# SCH-esp32.net
KiCad netlist of a schematic drawn in Altium Designer
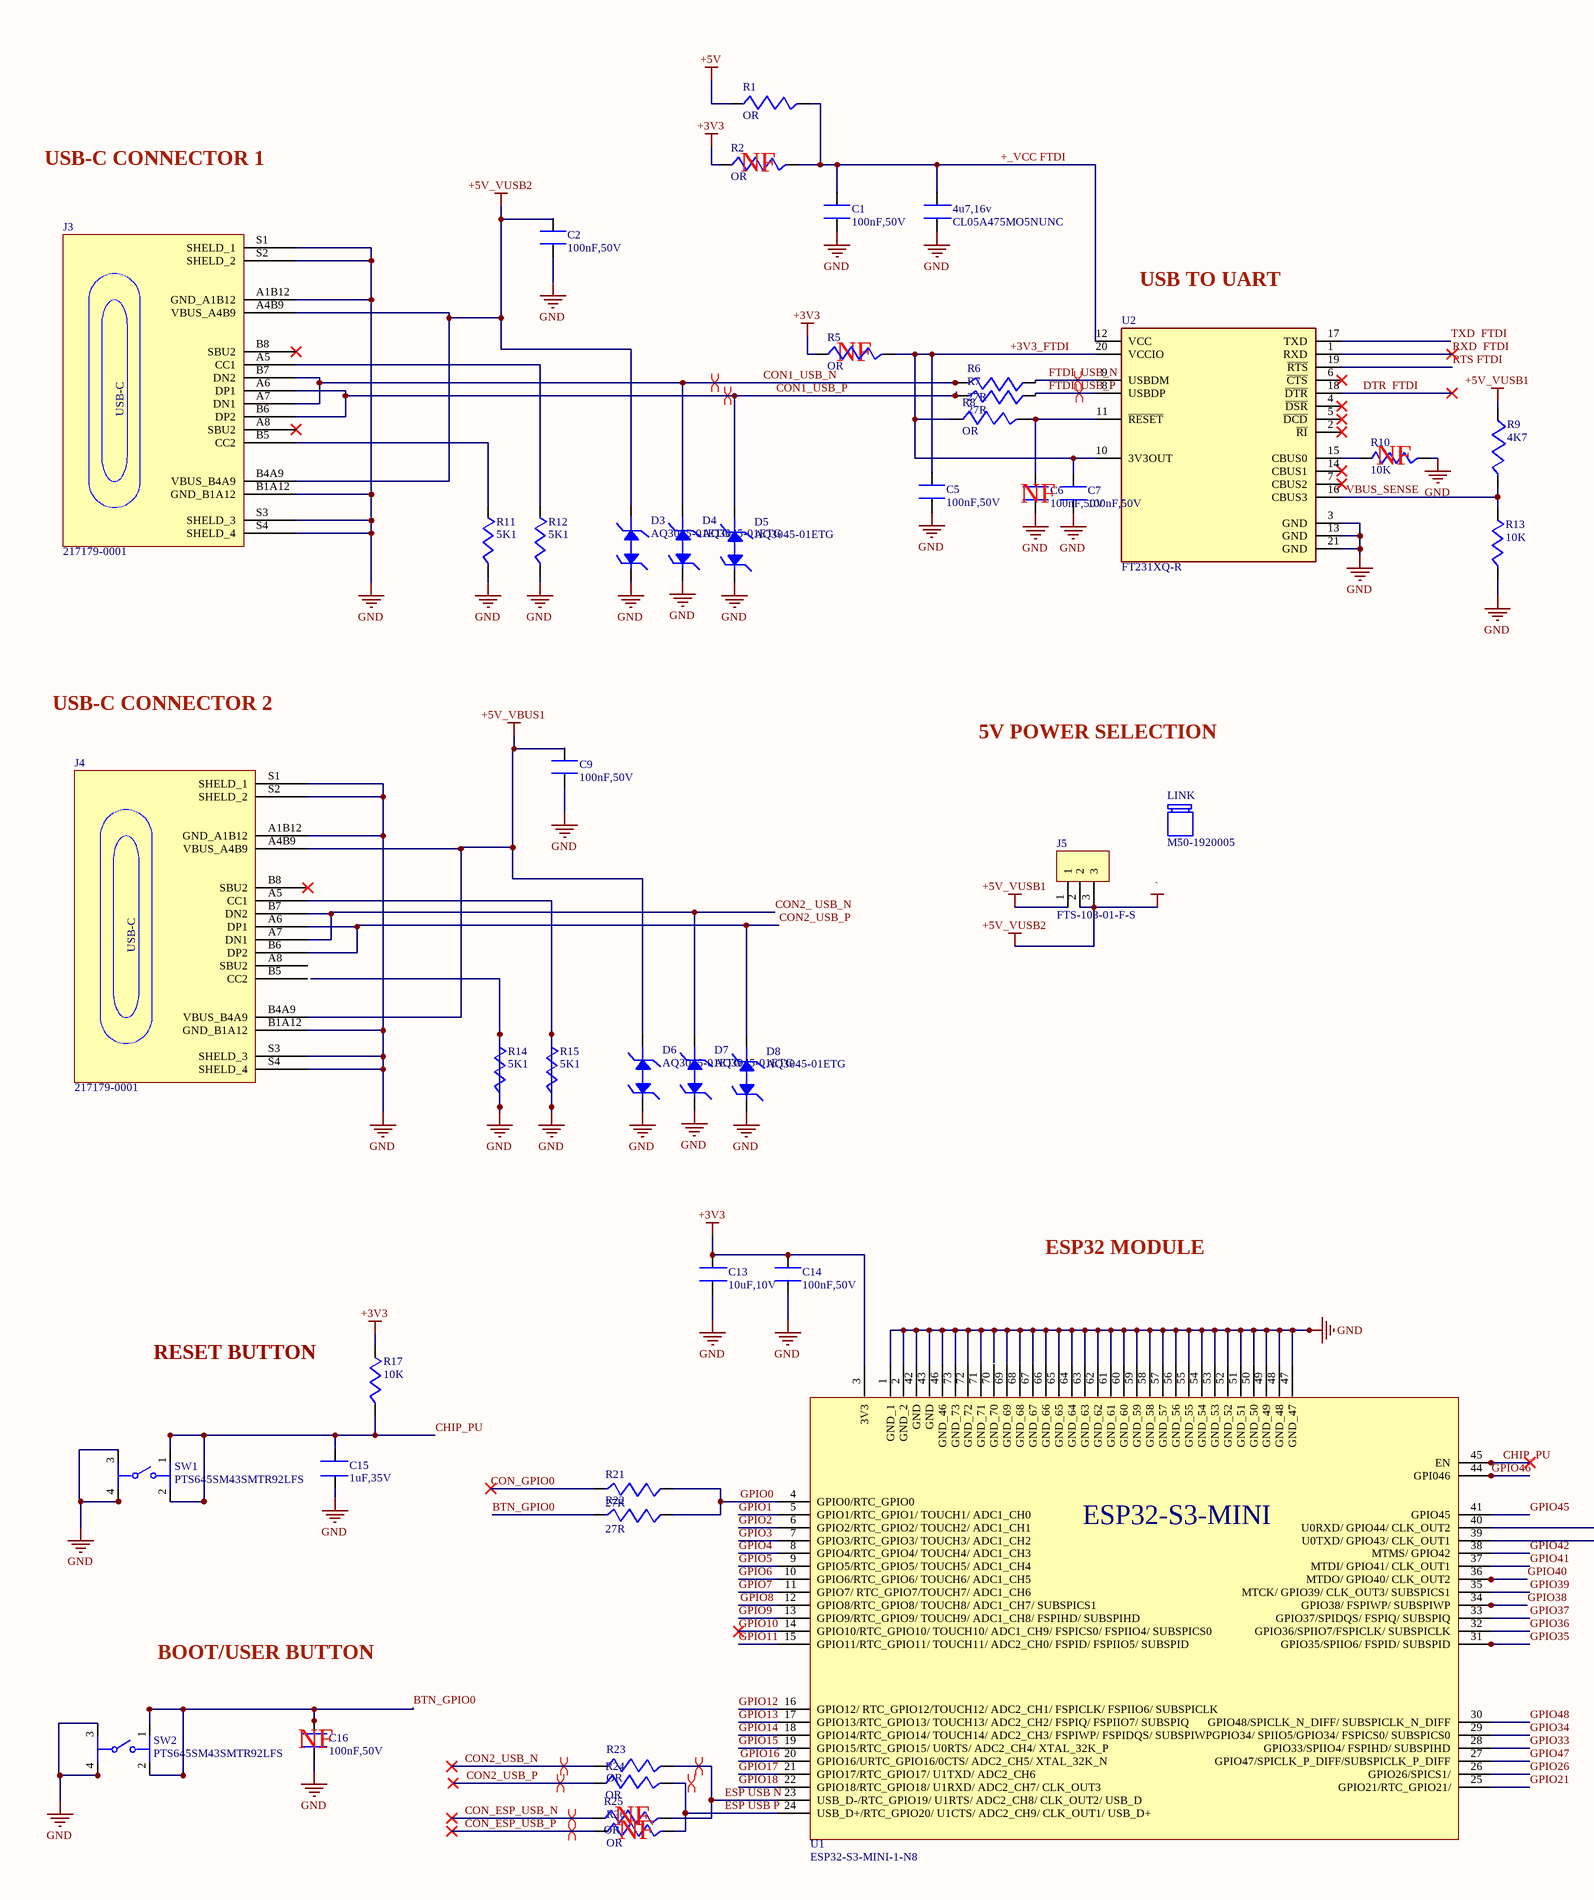
[diagram p0: SCH-esp32.SchDoc, left]
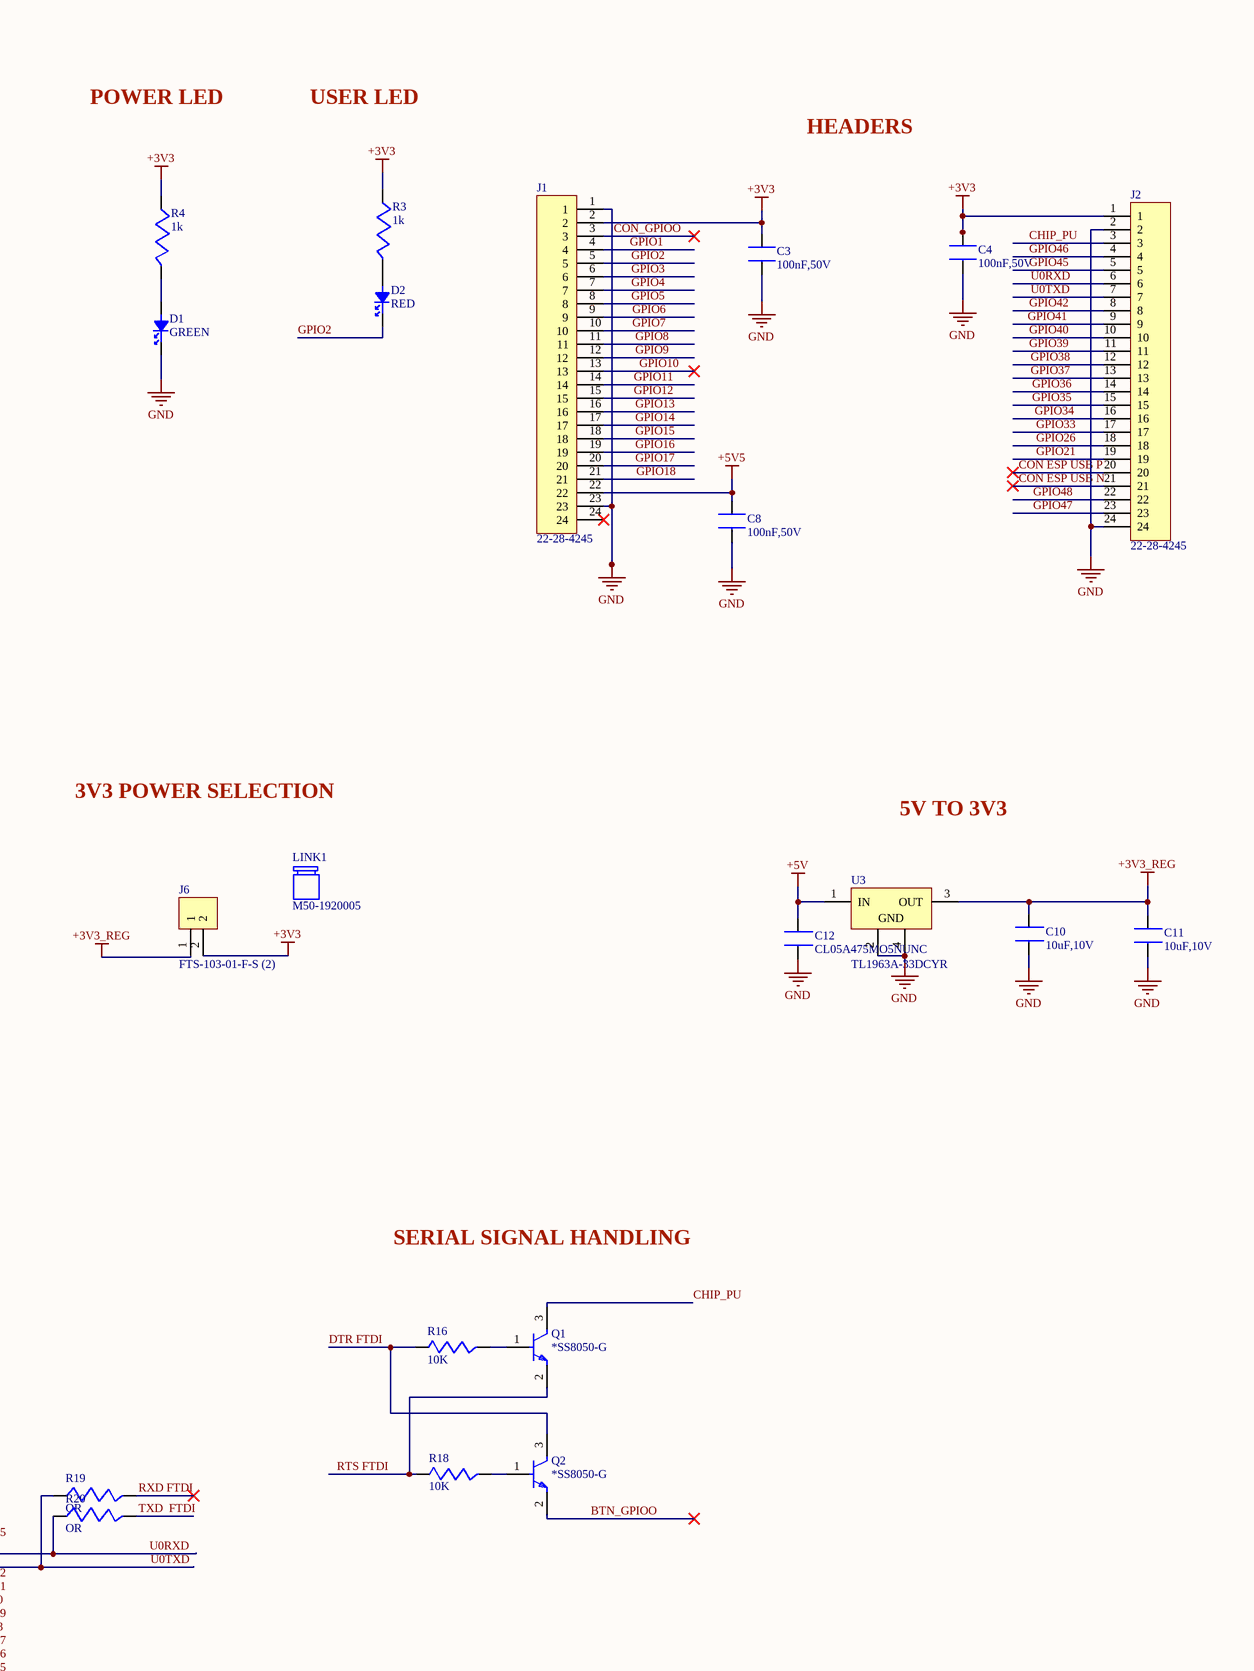
[diagram p1: SCH-esp32.SchDoc, right]

(export (version "E")
  (design (tool "Eeschema 10.0.6"))
  (components
    (comp (ref "4u7,16v")
      (value "CL05A475MO5NUNC")
      (footprint "CAPC1005X55N")
      (description "1276-6836-6-ND")
      (fields (field (name "MANUFACTURER") "Samsung Electro-Mechanics") (field (name "TOLERANCE") "20%"))
      (libsource (lib "Schlib-esp32") (part "CL05A475MO5NUNC"))
    )
    (comp (ref "C1")
      (value "100nF,50V")
      (footprint "CAPC1005X55N")
      (description "CAP CER 0.1UF 50V X7R 0402")
      (fields
        (field (name "MANUFACTURER") "Samsung Electro-Mechanics")
        (field (name "MANUFACTURER PART NUMBER") "CL05B104KB5NNNC")
      )
      (libsource (lib "Schlib-esp32") (part "CL05B104KB5NNNC"))
    )
    (comp (ref "C2")
      (value "100nF,50V")
      (footprint "CAPC1005X55N")
      (description "CAP CER 0.1UF 50V X7R 0402")
      (fields
        (field (name "MANUFACTURER") "Samsung Electro-Mechanics")
        (field (name "MANUFACTURER PART NUMBER") "CL05B104KB5NNNC")
      )
      (libsource (lib "Schlib-esp32") (part "CL05B104KB5NNNC"))
    )
    (comp (ref "C3")
      (value "100nF,50V")
      (footprint "CAPC1005X55N")
      (description "CAP CER 0.1UF 50V X7R 0402")
      (fields
        (field (name "MANUFACTURER") "Samsung Electro-Mechanics")
        (field (name "MANUFACTURER PART NUMBER") "CL05B104KB5NNNC")
      )
      (libsource (lib "Schlib-esp32") (part "CL05B104KB5NNNC"))
    )
    (comp (ref "C4")
      (value "100nF,50V")
      (footprint "CAPC1005X55N")
      (description "CAP CER 0.1UF 50V X7R 0402")
      (fields
        (field (name "MANUFACTURER") "Samsung Electro-Mechanics")
        (field (name "MANUFACTURER PART NUMBER") "CL05B104KB5NNNC")
      )
      (libsource (lib "Schlib-esp32") (part "CL05B104KB5NNNC"))
    )
    (comp (ref "C5")
      (value "100nF,50V")
      (footprint "CAPC1005X55N")
      (description "CAP CER 0.1UF 50V X7R 0402")
      (fields
        (field (name "MANUFACTURER") "Samsung Electro-Mechanics")
        (field (name "MANUFACTURER PART NUMBER") "CL05B104KB5NNNC")
      )
      (libsource (lib "Schlib-esp32") (part "CL05B104KB5NNNC"))
    )
    (comp (ref "C6")
      (value "100nF,50V")
      (footprint "CAPC1005X55N")
      (description "CAP CER 0.1UF 50V X7R 0402")
      (fields
        (field (name "MANUFACTURER") "Samsung Electro-Mechanics")
        (field (name "MANUFACTURER PART NUMBER") "CL05B104KB5NNNC")
      )
      (libsource (lib "Schlib-esp32") (part "CL05B104KB5NNNC"))
    )
    (comp (ref "C7")
      (value "100nF,50V")
      (footprint "CAPC1005X55N")
      (description "CAP CER 0.1UF 50V X7R 0402")
      (fields
        (field (name "MANUFACTURER") "Samsung Electro-Mechanics")
        (field (name "MANUFACTURER PART NUMBER") "CL05B104KB5NNNC")
      )
      (libsource (lib "Schlib-esp32") (part "CL05B104KB5NNNC"))
    )
    (comp (ref "C8")
      (value "100nF,50V")
      (footprint "CAPC1005X55N")
      (description "CAP CER 0.1UF 50V X7R 0402")
      (fields
        (field (name "MANUFACTURER") "Samsung Electro-Mechanics")
        (field (name "MANUFACTURER PART NUMBER") "CL05B104KB5NNNC")
      )
      (libsource (lib "Schlib-esp32") (part "CL05B104KB5NNNC"))
    )
    (comp (ref "C9")
      (value "100nF,50V")
      (footprint "CAPC1005X55N")
      (description "CAP CER 0.1UF 50V X7R 0402")
      (fields
        (field (name "MANUFACTURER") "Samsung Electro-Mechanics")
        (field (name "MANUFACTURER PART NUMBER") "CL05B104KB5NNNC")
      )
      (libsource (lib "Schlib-esp32") (part "CL05B104KB5NNNC"))
    )
    (comp (ref "C10")
      (value "10uF,10V")
      (footprint "CAPC1005X55N")
      (description "10V 10uF X5R ±20% 0402 Multilayer Ceramic Capacitors MLCC - SMD/SMT ROHS")
      (fields
        (field (name "MANUFACTURER") "Samsung Electro-Mechanics")
        (field (name "MANUFACTURER PART NUMBER") "CL05A106MP8NUB8")
      )
      (libsource (lib "Schlib-esp32") (part "CL05A106MP8NUB8"))
    )
    (comp (ref "C11")
      (value "10uF,10V")
      (footprint "CAPC1005X55N")
      (description "10V 10uF X5R ±20% 0402 Multilayer Ceramic Capacitors MLCC - SMD/SMT ROHS")
      (fields
        (field (name "MANUFACTURER") "Samsung Electro-Mechanics")
        (field (name "MANUFACTURER PART NUMBER") "CL05A106MP8NUB8")
      )
      (libsource (lib "Schlib-esp32") (part "CL05A106MP8NUB8"))
    )
    (comp (ref "C12")
      (value "CL05A475MO5NUNC")
      (footprint "CAPC1005X55N")
      (description "1276-6836-6-ND")
      (fields (field (name "MANUFACTURER") "Samsung Electro-Mechanics") (field (name "TOLERANCE") "20%"))
      (libsource (lib "Schlib-esp32") (part "CL05A475MO5NUNC"))
    )
    (comp (ref "C13")
      (value "10uF,10V")
      (footprint "CAPC1005X55N")
      (description "10V 10uF X5R ±20% 0402 Multilayer Ceramic Capacitors MLCC - SMD/SMT ROHS")
      (fields
        (field (name "MANUFACTURER") "Samsung Electro-Mechanics")
        (field (name "MANUFACTURER PART NUMBER") "CL05A106MP8NUB8")
      )
      (libsource (lib "Schlib-esp32") (part "CL05A106MP8NUB8"))
    )
    (comp (ref "C14")
      (value "100nF,50V")
      (footprint "CAPC1005X55N")
      (description "CAP CER 0.1UF 50V X7R 0402")
      (fields
        (field (name "MANUFACTURER") "Samsung Electro-Mechanics")
        (field (name "MANUFACTURER PART NUMBER") "CL05B104KB5NNNC")
      )
      (libsource (lib "Schlib-esp32") (part "CL05B104KB5NNNC"))
    )
    (comp (ref "C15")
      (value "1uF,35V")
      (footprint "CAPC1005X55N")
      (description "CAP CER 1UF 35V X5R 0402")
      (fields
        (field (name "MANUFACTURER") "Samsung Electro-Mechanics")
        (field (name "MANUFACTURER PART NUMBER") "CL05A105KL5NRNC")
      )
      (libsource (lib "Schlib-esp32") (part "CL05A105KL5NRNC"))
    )
    (comp (ref "C16")
      (value "100nF,50V")
      (footprint "CAPC1005X55N")
      (description "CAP CER 0.1UF 50V X7R 0402")
      (fields
        (field (name "MANUFACTURER") "Samsung Electro-Mechanics")
        (field (name "MANUFACTURER PART NUMBER") "CL05B104KB5NNNC")
      )
      (libsource (lib "Schlib-esp32") (part "CL05B104KB5NNNC"))
    )
    (comp (ref "D1")
      (value "GREEN")
      (footprint "LED0402G")
      (description "LED GREEN 0402 SMD")
      (fields
        (field (name "MANUFACTURER") "Vishay")
        (field (name "MANUFACTURER PART NUMBER") "VLMTG1500-GS08")
      )
      (libsource (lib "Schlib-esp32") (part "VLMTG1500-GS08"))
    )
    (comp (ref "D2")
      (value "RED")
      (footprint "LED0402R")
      (description "LED RED 0402 SMD")
      (fields
        (field (name "MANUFACTURER") "Vishay")
        (field (name "MANUFACTURER PART NUMBER") "VLMS1500-GS08")
      )
      (libsource (lib "Schlib-esp32") (part "VLMS1500-GS08"))
    )
    (comp (ref "D3")
      (value "AQ3045-01ETG")
      (footprint "SOD882")
      (description "TVS DIODE 5.3VWM 12VC SOD882")
      (fields (field (name "MANUFACTURER") "Littelfuse"))
      (libsource (lib "Schlib-esp32") (part "AQ3045-01ETG"))
    )
    (comp (ref "D4")
      (value "AQ3045-01ETG")
      (footprint "SOD882")
      (description "TVS DIODE 5.3VWM 12VC SOD882")
      (fields (field (name "MANUFACTURER") "Littelfuse"))
      (libsource (lib "Schlib-esp32") (part "AQ3045-01ETG"))
    )
    (comp (ref "D5")
      (value "AQ3045-01ETG")
      (footprint "SOD882")
      (description "TVS DIODE 5.3VWM 12VC SOD882")
      (fields (field (name "MANUFACTURER") "Littelfuse"))
      (libsource (lib "Schlib-esp32") (part "AQ3045-01ETG"))
    )
    (comp (ref "D6")
      (value "AQ3045-01ETG")
      (footprint "SOD882")
      (description "TVS DIODE 5.3VWM 12VC SOD882")
      (fields (field (name "MANUFACTURER") "Littelfuse"))
      (libsource (lib "Schlib-esp32") (part "AQ3045-01ETG"))
    )
    (comp (ref "D7")
      (value "AQ3045-01ETG")
      (footprint "SOD882")
      (description "TVS DIODE 5.3VWM 12VC SOD882")
      (fields (field (name "MANUFACTURER") "Littelfuse"))
      (libsource (lib "Schlib-esp32") (part "AQ3045-01ETG"))
    )
    (comp (ref "D8")
      (value "AQ3045-01ETG")
      (footprint "SOD882")
      (description "TVS DIODE 5.3VWM 12VC SOD882")
      (fields (field (name "MANUFACTURER") "Littelfuse"))
      (libsource (lib "Schlib-esp32") (part "AQ3045-01ETG"))
    )
    (comp (ref "J1")
      (value "22-28-4245")
      (footprint "HDR_1X24_2.54MM")
      (description "CONN HEADER VERT 24POS 2.54MM")
      (fields (field (name "MANUFACTURER") "Molex"))
      (libsource (lib "") (part "22-28-4245_1"))
    )
    (comp (ref "J2")
      (value "22-28-4245")
      (footprint "HDR_1X24_2.54MM")
      (description "CONN HEADER VERT 24POS 2.54MM")
      (fields (field (name "MANUFACTURER") "Molex"))
      (libsource (lib "Schlib-esp32") (part "22-28-4245"))
    )
    (comp (ref "J3")
      (value "217179-0001")
      (footprint "FP-2171790001-MFG")
      (description "USB Connector, USB Type C, USB 2.0, Receptacle, 16 Ways, Surface Mount, Through Hole Mount")
      (fields (field (name "MANUFACTURER") "Molex"))
      (libsource (lib "Schlib-esp32") (part "217179-0001"))
    )
    (comp (ref "J4")
      (value "217179-0001")
      (footprint "FP-2171790001-MFG")
      (description "USB Connector, USB Type C, USB 2.0, Receptacle, 16 Ways, Surface Mount, Through Hole Mount")
      (fields (field (name "MANUFACTURER") "Molex"))
      (libsource (lib "Schlib-esp32") (part "217179-0001"))
    )
    (comp (ref "J5")
      (value "FTS-103-01-F-S")
      (footprint "HDR_1X3_1.27MM")
      (description "CONN HEADER VERT 3POS 1.27MM")
      (fields (field (name "MANUFACTURER") "Samtec"))
      (libsource (lib "Schlib-esp32") (part "FTS-103-01-F-S"))
    )
    (comp (ref "J6")
      (value "FTS-103-01-F-S (2)")
      (footprint "HDR_1X2_1.27MM")
      (description "CONN HEADER VERT 3POS 1.27MM")
      (fields
        (field (name "MANUFACTURER") "Samtec")
        (field (name "MANUFACTURER PART NUMBER") "FTS-103-01-F-S")
      )
      (libsource (lib "Schlib-esp32") (part "FTS-103-01-F-S (2)"))
    )
    (comp (ref "LINK")
      (value "M50-1920005")
      (description "2 (1 x 2) Position Shunt Connector Red Closed Top 0.050\" (1.27mm) Gold")
      (fields (field (name "MANUFACTURER") "Harwin"))
      (libsource (lib "Schlib-esp32") (part "M50-1920005"))
    )
    (comp (ref "LINK1")
      (value "M50-1920005")
      (description "2 (1 x 2) Position Shunt Connector Red Closed Top 0.050\" (1.27mm) Gold")
      (fields (field (name "MANUFACTURER") "Harwin"))
      (libsource (lib "Schlib-esp32") (part "M50-1920005"))
    )
    (comp (ref "Q1")
      (value "*SS8050-G")
      (footprint "FP-SS8050-G-IPC_B")
      (description "TRANS NPN 25V 1.5A SOT-23-3")
      (fields (field (name "MANUFACTURER") "Comchip") (field (name "MANUFACTURER PART NUMBER") "SS8050-G"))
      (libsource (lib "Schlib-esp32") (part "SS8050-G"))
    )
    (comp (ref "Q2")
      (value "*SS8050-G")
      (footprint "FP-SS8050-G-IPC_B")
      (description "TRANS NPN 25V 1.5A SOT-23-3")
      (fields (field (name "MANUFACTURER") "Comchip") (field (name "MANUFACTURER PART NUMBER") "SS8050-G"))
      (libsource (lib "Schlib-esp32") (part "SS8050-G"))
    )
    (comp (ref "R1")
      (value "OR")
      (footprint "RESC1005X37N")
      (description "RES 0 OHM JUMPER 1/16W 0402")
      (fields
        (field (name "MANUFACTURER") "Yageo Group")
        (field (name "MANUFACTURER PART NUMBER") "RC0402JR-070RL")
      )
      (libsource (lib "Schlib-esp32") (part "RC0402JR-070RL"))
    )
    (comp (ref "R2")
      (value "OR")
      (footprint "RESC1005X37N")
      (description "RES 0 OHM JUMPER 1/16W 0402")
      (fields
        (field (name "MANUFACTURER") "Yageo Group")
        (field (name "MANUFACTURER PART NUMBER") "RC0402JR-070RL")
      )
      (libsource (lib "Schlib-esp32") (part "RC0402JR-070RL"))
    )
    (comp (ref "R3")
      (value "1k")
      (footprint "RESC1005X37N")
      (description "RES 1K OHM 1% 1/16W 0402")
      (fields
        (field (name "MANUFACTURER") "Vishay")
        (field (name "MANUFACTURER PART NUMBER") "MCS0402PD1001DE500")
      )
      (libsource (lib "Schlib-esp32") (part "MCS0402PD1001DE500"))
    )
    (comp (ref "R4")
      (value "1k")
      (footprint "RESC1005X37N")
      (description "RES 1K OHM 1% 1/16W 0402")
      (fields
        (field (name "MANUFACTURER") "Vishay")
        (field (name "MANUFACTURER PART NUMBER") "MCS0402PD1001DE500")
      )
      (libsource (lib "Schlib-esp32") (part "MCS0402PD1001DE500"))
    )
    (comp (ref "R5")
      (value "OR")
      (footprint "RESC1005X37N")
      (description "RES 0 OHM JUMPER 1/16W 0402")
      (fields
        (field (name "MANUFACTURER") "Yageo Group")
        (field (name "MANUFACTURER PART NUMBER") "RC0402JR-070RL")
      )
      (libsource (lib "Schlib-esp32") (part "RC0402JR-070RL"))
    )
    (comp (ref "R6")
      (value "27R")
      (footprint "RESC1005X37N")
      (description "RES 27 OHM 1% 1/16W 0402")
      (fields
        (field (name "MANUFACTURER") "Yageo Group")
        (field (name "MANUFACTURER PART NUMBER") "RC0402FR-0727RL")
      )
      (libsource (lib "Schlib-esp32") (part "RC0402FR-0727RL"))
    )
    (comp (ref "R7")
      (value "27R")
      (footprint "RESC1005X37N")
      (description "RES 27 OHM 1% 1/16W 0402")
      (fields
        (field (name "MANUFACTURER") "Yageo Group")
        (field (name "MANUFACTURER PART NUMBER") "RC0402FR-0727RL")
      )
      (libsource (lib "Schlib-esp32") (part "RC0402FR-0727RL"))
    )
    (comp (ref "R8")
      (value "OR")
      (footprint "RESC1005X37N")
      (description "RES 0 OHM JUMPER 1/16W 0402")
      (fields
        (field (name "MANUFACTURER") "Yageo Group")
        (field (name "MANUFACTURER PART NUMBER") "RC0402JR-070RL")
      )
      (libsource (lib "Schlib-esp32") (part "RC0402JR-070RL"))
    )
    (comp (ref "R9")
      (value "4K7")
      (footprint "RESC1005X37N")
      (description "RES 4.7K OHM 1% 1/16W 0402")
      (fields
        (field (name "MANUFACTURER") "Yageo Group")
        (field (name "MANUFACTURER PART NUMBER") "AC0603JR-134K7L")
      )
      (libsource (lib "Schlib-esp32") (part "AC0603JR-134K7L"))
    )
    (comp (ref "R10")
      (value "10K")
      (footprint "RESC1005X37N")
      (description "RES SMD 10K OHM 1% 1/16W 0402")
      (fields
        (field (name "MANUFACTURER") "Yageo Group")
        (field (name "MANUFACTURER PART NUMBER") "AC0402FR-0710KL")
      )
      (libsource (lib "Schlib-esp32") (part "AC0402FR-0710KL"))
    )
    (comp (ref "R11")
      (value "5K1")
      (footprint "RESC1005X37N")
      (description "RES SMD 5.1K OHM 1% 1/16W 0402")
      (fields
        (field (name "MANUFACTURER") "Yageo Group")
        (field (name "MANUFACTURER PART NUMBER") "AC0402FR-075K1L")
      )
      (libsource (lib "Schlib-esp32") (part "AC0402FR-075K1L"))
    )
    (comp (ref "R12")
      (value "5K1")
      (footprint "RESC1005X37N")
      (description "RES SMD 5.1K OHM 1% 1/16W 0402")
      (fields
        (field (name "MANUFACTURER") "Yageo Group")
        (field (name "MANUFACTURER PART NUMBER") "AC0402FR-075K1L")
      )
      (libsource (lib "Schlib-esp32") (part "AC0402FR-075K1L"))
    )
    (comp (ref "R13")
      (value "10K")
      (footprint "RESC1005X37N")
      (description "RES SMD 10K OHM 1% 1/16W 0402")
      (fields
        (field (name "MANUFACTURER") "Yageo Group")
        (field (name "MANUFACTURER PART NUMBER") "AC0402FR-0710KL")
      )
      (libsource (lib "Schlib-esp32") (part "AC0402FR-0710KL"))
    )
    (comp (ref "R14")
      (value "5K1")
      (footprint "RESC1005X37N")
      (description "RES SMD 5.1K OHM 1% 1/16W 0402")
      (fields
        (field (name "MANUFACTURER") "Yageo Group")
        (field (name "MANUFACTURER PART NUMBER") "AC0402FR-075K1L")
      )
      (libsource (lib "Schlib-esp32") (part "AC0402FR-075K1L"))
    )
    (comp (ref "R15")
      (value "5K1")
      (footprint "RESC1005X37N")
      (description "RES SMD 5.1K OHM 1% 1/16W 0402")
      (fields
        (field (name "MANUFACTURER") "Yageo Group")
        (field (name "MANUFACTURER PART NUMBER") "AC0402FR-075K1L")
      )
      (libsource (lib "Schlib-esp32") (part "AC0402FR-075K1L"))
    )
    (comp (ref "R16")
      (value "10K")
      (footprint "RESC1005X37N")
      (description "RES SMD 10K OHM 1% 1/16W 0402")
      (fields
        (field (name "MANUFACTURER") "Yageo Group")
        (field (name "MANUFACTURER PART NUMBER") "AC0402FR-0710KL")
      )
      (libsource (lib "Schlib-esp32") (part "AC0402FR-0710KL"))
    )
    (comp (ref "R17")
      (value "10K")
      (footprint "RESC1005X37N")
      (description "RES SMD 10K OHM 1% 1/16W 0402")
      (fields
        (field (name "MANUFACTURER") "Yageo Group")
        (field (name "MANUFACTURER PART NUMBER") "AC0402FR-0710KL")
      )
      (libsource (lib "Schlib-esp32") (part "AC0402FR-0710KL"))
    )
    (comp (ref "R18")
      (value "10K")
      (footprint "RESC1005X37N")
      (description "RES SMD 10K OHM 1% 1/16W 0402")
      (fields
        (field (name "MANUFACTURER") "Yageo Group")
        (field (name "MANUFACTURER PART NUMBER") "AC0402FR-0710KL")
      )
      (libsource (lib "Schlib-esp32") (part "AC0402FR-0710KL"))
    )
    (comp (ref "R19")
      (value "OR")
      (footprint "RESC1005X37N")
      (description "RES 0 OHM JUMPER 1/16W 0402")
      (fields
        (field (name "MANUFACTURER") "Yageo Group")
        (field (name "MANUFACTURER PART NUMBER") "RC0402JR-070RL")
      )
      (libsource (lib "Schlib-esp32") (part "RC0402JR-070RL"))
    )
    (comp (ref "R20")
      (value "OR")
      (footprint "RESC1005X37N")
      (description "RES 0 OHM JUMPER 1/16W 0402")
      (fields
        (field (name "MANUFACTURER") "Yageo Group")
        (field (name "MANUFACTURER PART NUMBER") "RC0402JR-070RL")
      )
      (libsource (lib "Schlib-esp32") (part "RC0402JR-070RL"))
    )
    (comp (ref "R21")
      (value "27R")
      (footprint "RESC1005X37N")
      (description "RES 27 OHM 1% 1/16W 0402")
      (fields
        (field (name "MANUFACTURER") "Yageo Group")
        (field (name "MANUFACTURER PART NUMBER") "RC0402FR-0727RL")
      )
      (libsource (lib "Schlib-esp32") (part "RC0402FR-0727RL"))
    )
    (comp (ref "R22")
      (value "27R")
      (footprint "RESC1005X37N")
      (description "RES 27 OHM 1% 1/16W 0402")
      (fields
        (field (name "MANUFACTURER") "Yageo Group")
        (field (name "MANUFACTURER PART NUMBER") "RC0402FR-0727RL")
      )
      (libsource (lib "Schlib-esp32") (part "RC0402FR-0727RL"))
    )
    (comp (ref "R23")
      (value "OR")
      (footprint "RESC1005X37N")
      (description "RES 0 OHM JUMPER 1/16W 0402")
      (fields
        (field (name "MANUFACTURER") "Yageo Group")
        (field (name "MANUFACTURER PART NUMBER") "RC0402JR-070RL")
      )
      (libsource (lib "Schlib-esp32") (part "RC0402JR-070RL"))
    )
    (comp (ref "R24")
      (value "OR")
      (footprint "RESC1005X37N")
      (description "RES 0 OHM JUMPER 1/16W 0402")
      (fields
        (field (name "MANUFACTURER") "Yageo Group")
        (field (name "MANUFACTURER PART NUMBER") "RC0402JR-070RL")
      )
      (libsource (lib "Schlib-esp32") (part "RC0402JR-070RL"))
    )
    (comp (ref "R25")
      (value "OR")
      (footprint "RESC1005X37N")
      (description "RES 0 OHM JUMPER 1/16W 0402")
      (fields
        (field (name "MANUFACTURER") "Yageo Group")
        (field (name "MANUFACTURER PART NUMBER") "RC0402JR-070RL")
      )
      (libsource (lib "Schlib-esp32") (part "RC0402JR-070RL"))
    )
    (comp (ref "R26")
      (value "OR")
      (footprint "RESC1005X37N")
      (description "RES 0 OHM JUMPER 1/16W 0402")
      (fields
        (field (name "MANUFACTURER") "Yageo Group")
        (field (name "MANUFACTURER PART NUMBER") "RC0402JR-070RL")
      )
      (libsource (lib "Schlib-esp32") (part "RC0402JR-070RL"))
    )
    (comp (ref "SW1")
      (value "PTS645SM43SMTR92LFS")
      (footprint "FP-PTS645SH50SMTR92LFS-MFG")
      (description "SWITCH TACTILE SPST-NO 0.05A 12V")
      (fields (field (name "MANUFACTURER") "C&K Components"))
      (libsource (lib "Schlib-esp32") (part "PTS645SM43SMTR92LFS"))
    )
    (comp (ref "SW2")
      (value "PTS645SM43SMTR92LFS")
      (footprint "FP-PTS645SH50SMTR92LFS-MFG")
      (description "SWITCH TACTILE SPST-NO 0.05A 12V")
      (fields (field (name "MANUFACTURER") "C&K Components"))
      (libsource (lib "Schlib-esp32") (part "PTS645SM43SMTR92LFS"))
    )
    (comp (ref "U1")
      (value "ESP32-S3-MINI-1-N8")
      (footprint "XCVR_ESP32-S3-MINI-1-N8 - duplicate")
      (description "SMD module, ESP32-S3FN8, 8 MB SPI flash, PCB antenna")
      (fields (field (name "MANUFACTURER") "Espressif Systems"))
      (libsource (lib "Schlib-esp32") (part "ESP32-S3-MINI-1-N8"))
    )
    (comp (ref "U2")
      (value "FT231XQ-R")
      (footprint "FP-QFN-20-IPC_B")
      (description "IC USB SERIAL FULL UART 20QFN")
      (fields (field (name "MANUFACTURER") "FTDI"))
      (libsource (lib "Schlib-esp32") (part "FT231XQ-R"))
    )
    (comp (ref "U3")
      (value "TL1963A-33DCYR")
      (footprint "DCY0004A_N")
      (description "IC REG LIN 3.3V 1.5A SOT-223-4")
      (fields (field (name "MANUFACTURER") "Texas Instruments"))
      (libsource (lib "Schlib-esp32") (part "TL1963A-33DCYR"))
    )
  )
  (nets
    (net (code "1") (name "+3V3") (class "Default")
      (node (ref "C13") (pin "2") (pinfunction "2_2") (pintype "passive"))
      (node (ref "C14") (pin "2") (pinfunction "2_2") (pintype "passive"))
      (node (ref "C3") (pin "2") (pinfunction "2_2") (pintype "passive"))
      (node (ref "C4") (pin "2") (pinfunction "2_2") (pintype "passive"))
      (node (ref "J1") (pin "2") (pinfunction "2_2") (pintype "passive"))
      (node (ref "J2") (pin "1") (pinfunction "1_1") (pintype "passive"))
      (node (ref "J6") (pin "2") (pinfunction "2_2") (pintype "passive"))
      (node (ref "R17") (pin "2") (pinfunction "2_2") (pintype "passive"))
      (node (ref "R2") (pin "2") (pinfunction "2_2") (pintype "passive"))
      (node (ref "R3") (pin "2") (pinfunction "2_2") (pintype "passive"))
      (node (ref "R4") (pin "2") (pinfunction "2_2") (pintype "passive"))
      (node (ref "R5") (pin "2") (pinfunction "2_2") (pintype "passive"))
      (node (ref "U1") (pin "3") (pinfunction "3V3_3") (pintype "passive"))
    )
    (net (code "2") (name "+3V3_REG") (class "Default")
      (node (ref "C10") (pin "2") (pinfunction "2_2") (pintype "passive"))
      (node (ref "C11") (pin "2") (pinfunction "2_2") (pintype "passive"))
      (node (ref "J6") (pin "1") (pinfunction "1_1") (pintype "passive"))
      (node (ref "U3") (pin "3") (pinfunction "OUT_3") (pintype "power_in"))
    )
    (net (code "3") (name "+5V") (class "Default")
      (node (ref "C12") (pin "2") (pinfunction "2_2") (pintype "passive"))
      (node (ref "R1") (pin "2") (pinfunction "2_2") (pintype "passive"))
      (node (ref "U3") (pin "1") (pinfunction "IN_1") (pintype "power_in"))
    )
    (net (code "4") (name "+5V5") (class "Default")
      (node (ref "C8") (pin "2") (pinfunction "2_2") (pintype "passive"))
      (node (ref "J1") (pin "22") (pinfunction "22_22") (pintype "passive"))
    )
    (net (code "5") (name "+5V_VBUS1") (class "Default")
      (node (ref "C9") (pin "2") (pinfunction "2_2") (pintype "passive"))
      (node (ref "D6") (pin "2") (pinfunction "2_2") (pintype "passive"))
      (node (ref "J4") (pin "A4B9") (pinfunction "_VBUS_A4B9_A4B9") (pintype "passive"))
      (node (ref "J4") (pin "B4A9") (pinfunction "VBUS_B4A9_B4A9") (pintype "passive"))
    )
    (net (code "6") (name "+5V_VUSB1") (class "Default")
      (node (ref "J5") (pin "1") (pinfunction "1_1") (pintype "passive"))
      (node (ref "R9") (pin "2") (pinfunction "2_2") (pintype "passive"))
    )
    (net (code "7") (name "+5V_VUSB2") (class "Default")
      (node (ref "C2") (pin "2") (pinfunction "2_2") (pintype "passive"))
      (node (ref "D3") (pin "2") (pinfunction "2_2") (pintype "passive"))
      (node (ref "J3") (pin "A4B9") (pinfunction "_VBUS_A4B9_A4B9") (pintype "passive"))
      (node (ref "J3") (pin "B4A9") (pinfunction "VBUS_B4A9_B4A9") (pintype "passive"))
      (node (ref "J5") (pin "2") (pinfunction "2_2") (pintype "passive"))
      (node (ref "J5") (pin "3") (pinfunction "3_3") (pintype "passive"))
    )
    (net (code "8") (name "/+3V3_FTDI") (class "Default")
      (node (ref "C5") (pin "2") (pinfunction "2_2") (pintype "passive"))
      (node (ref "C7") (pin "2") (pinfunction "2_2") (pintype "passive"))
      (node (ref "R5") (pin "1") (pinfunction "1_1") (pintype "passive"))
      (node (ref "R8") (pin "2") (pinfunction "2_2") (pintype "passive"))
      (node (ref "U2") (pin "10") (pinfunction "3V3OUT_10") (pintype "passive"))
      (node (ref "U2") (pin "20") (pinfunction "VCCIO_20") (pintype "passive"))
    )
    (net (code "9") (name "/+_VCC FTDI") (class "Default")
      (node (ref "4u7,16v") (pin "2") (pinfunction "2_2") (pintype "passive"))
      (node (ref "C1") (pin "2") (pinfunction "2_2") (pintype "passive"))
      (node (ref "R1") (pin "1") (pinfunction "1_1") (pintype "passive"))
      (node (ref "R2") (pin "1") (pinfunction "1_1") (pintype "passive"))
      (node (ref "U2") (pin "12") (pinfunction "VCC_12") (pintype "passive"))
    )
    (net (code "10") (name "/BTN_GPIO0") (class "Default")
      (node (ref "C16") (pin "2") (pinfunction "2_2") (pintype "passive"))
      (node (ref "R22") (pin "1") (pinfunction "1_1") (pintype "passive"))
      (node (ref "SW2") (pin "1") (pinfunction "1_1") (pintype "passive"))
      (node (ref "SW2") (pin "2") (pinfunction "2_2") (pintype "passive"))
    )
    (net (code "11") (name "/BTN_GPIOO") (class "Default")
      (node (ref "Q2") (pin "2") (pinfunction "E_2") (pintype "passive+no_connect"))
    )
    (net (code "12") (name "/CHIP_PU") (class "Default")
      (node (ref "C15") (pin "2") (pinfunction "2_2") (pintype "passive"))
      (node (ref "J2") (pin "3") (pinfunction "3_3") (pintype "passive"))
      (node (ref "Q1") (pin "3") (pinfunction "C_3") (pintype "passive"))
      (node (ref "R17") (pin "1") (pinfunction "1_1") (pintype "passive"))
      (node (ref "SW1") (pin "1") (pinfunction "1_1") (pintype "passive"))
      (node (ref "SW1") (pin "2") (pinfunction "2_2") (pintype "passive"))
      (node (ref "U1") (pin "45") (pinfunction "EN_45") (pintype "passive"))
    )
    (net (code "13") (name "/CON ESP USB N") (class "Default")
      (node (ref "J2") (pin "21") (pinfunction "21_21") (pintype "passive+no_connect"))
    )
    (net (code "14") (name "/CON ESP USB P") (class "Default")
      (node (ref "J2") (pin "20") (pinfunction "20_20") (pintype "passive+no_connect"))
    )
    (net (code "15") (name "/CON1_USB_N") (class "Default")
      (node (ref "D4") (pin "2") (pinfunction "2_2") (pintype "passive"))
      (node (ref "J3") (pin "A7") (pinfunction "_DN1_A7") (pintype "passive"))
      (node (ref "J3") (pin "B7") (pinfunction "DN2_B7") (pintype "passive"))
      (node (ref "R6") (pin "1") (pinfunction "1_1") (pintype "passive"))
    )
    (net (code "16") (name "/CON1_USB_P") (class "Default")
      (node (ref "D5") (pin "2") (pinfunction "2_2") (pintype "passive"))
      (node (ref "J3") (pin "A6") (pinfunction "_DP1_A6") (pintype "passive"))
      (node (ref "J3") (pin "B6") (pinfunction "DP2_B6") (pintype "passive"))
      (node (ref "R7") (pin "1") (pinfunction "1_1") (pintype "passive"))
    )
    (net (code "17") (name "/CON2_ USB_N") (class "Default")
      (node (ref "D7") (pin "2") (pinfunction "2_2") (pintype "passive"))
      (node (ref "J4") (pin "A7") (pinfunction "_DN1_A7") (pintype "passive"))
      (node (ref "J4") (pin "B7") (pinfunction "DN2_B7") (pintype "passive"))
    )
    (net (code "18") (name "/CON2_USB_N") (class "Default")
      (node (ref "R23") (pin "2") (pinfunction "2_2") (pintype "passive+no_connect"))
    )
    (net (code "19") (name "/CON2_USB_P") (class "Default")
      (node (ref "D8") (pin "2") (pinfunction "2_2") (pintype "passive"))
      (node (ref "J4") (pin "A6") (pinfunction "_DP1_A6") (pintype "passive"))
      (node (ref "J4") (pin "B6") (pinfunction "DP2_B6") (pintype "passive"))
      (node (ref "R24") (pin "2") (pinfunction "2_2") (pintype "passive"))
    )
    (net (code "20") (name "/CON_ESP_USB_N") (class "Default")
      (node (ref "R25") (pin "2") (pinfunction "2_2") (pintype "passive+no_connect"))
    )
    (net (code "21") (name "/CON_ESP_USB_P") (class "Default")
      (node (ref "R26") (pin "2") (pinfunction "2_2") (pintype "passive+no_connect"))
    )
    (net (code "22") (name "/CON_GPIO0") (class "Default")
      (node (ref "R21") (pin "1") (pinfunction "1_1") (pintype "passive+no_connect"))
    )
    (net (code "23") (name "/CON_GPIOO") (class "Default")
      (node (ref "J1") (pin "3") (pinfunction "3_3") (pintype "passive+no_connect"))
    )
    (net (code "24") (name "/DTR  FTDI") (class "Default")
      (node (ref "U2") (pin "18") (pinfunction "~{DTR}_18") (pintype "passive+no_connect"))
    )
    (net (code "25") (name "/DTR FTDI") (class "Default")
      (node (ref "Q2") (pin "3") (pinfunction "C_3") (pintype "passive"))
      (node (ref "R16") (pin "2") (pinfunction "2_2") (pintype "passive"))
    )
    (net (code "26") (name "/ESP USB N") (class "Default")
      (node (ref "R23") (pin "1") (pinfunction "1_1") (pintype "passive"))
      (node (ref "R25") (pin "1") (pinfunction "1_1") (pintype "passive"))
      (node (ref "U1") (pin "23") (pinfunction "USB_D-/RTC_GPIO19/_U1RTS/_ADC2_CH8/_CLK_OUT2/_USB_D_23") (pintype "passive"))
    )
    (net (code "27") (name "/ESP USB P") (class "Default")
      (node (ref "R24") (pin "1") (pinfunction "1_1") (pintype "passive"))
      (node (ref "R26") (pin "1") (pinfunction "1_1") (pintype "passive"))
      (node (ref "U1") (pin "24") (pinfunction "USB_D+/RTC_GPIO20/_U1CTS/_ADC2_CH9/_CLK_OUT1/_USB_D+_24") (pintype "passive"))
    )
    (net (code "28") (name "/FTDI_USB_N") (class "Default")
      (node (ref "R6") (pin "2") (pinfunction "2_2") (pintype "passive"))
      (node (ref "U2") (pin "9") (pinfunction "USBDM_9") (pintype "passive"))
    )
    (net (code "29") (name "/FTDI_USB_P") (class "Default")
      (node (ref "R7") (pin "2") (pinfunction "2_2") (pintype "passive"))
      (node (ref "U2") (pin "8") (pinfunction "USBDP_8") (pintype "passive"))
    )
    (net (code "30") (name "/GPIO0") (class "Default")
      (node (ref "R21") (pin "2") (pinfunction "2_2") (pintype "passive"))
      (node (ref "R22") (pin "2") (pinfunction "2_2") (pintype "passive"))
      (node (ref "U1") (pin "4") (pinfunction "GPIO0/RTC_GPIO0_4") (pintype "passive"))
    )
    (net (code "31") (name "/GPIO1") (class "Default")
      (node (ref "J1") (pin "4") (pinfunction "4_4") (pintype "passive"))
      (node (ref "U1") (pin "5") (pinfunction "GPIO1/RTC_GPIO1/_TOUCH1/_ADC1_CH0_5") (pintype "passive"))
    )
    (net (code "32") (name "/GPIO2") (class "Default")
      (node (ref "D2") (pin "1") (pinfunction "1_1") (pintype "passive"))
      (node (ref "J1") (pin "5") (pinfunction "5_5") (pintype "passive"))
      (node (ref "U1") (pin "6") (pinfunction "GPIO2/RTC_GPIO2/_TOUCH2/_ADC1_CH1_6") (pintype "passive"))
    )
    (net (code "33") (name "/GPIO3") (class "Default")
      (node (ref "J1") (pin "6") (pinfunction "6_6") (pintype "passive"))
      (node (ref "U1") (pin "7") (pinfunction "GPIO3/RTC_GPIO3/_TOUCH3/_ADC1_CH2_7") (pintype "passive"))
    )
    (net (code "34") (name "/GPIO4") (class "Default")
      (node (ref "J1") (pin "7") (pinfunction "7_7") (pintype "passive"))
      (node (ref "U1") (pin "8") (pinfunction "GPIO4/RTC_GPIO4/_TOUCH4/_ADC1_CH3_8") (pintype "passive"))
    )
    (net (code "35") (name "/GPIO5") (class "Default")
      (node (ref "J1") (pin "8") (pinfunction "8_8") (pintype "passive"))
      (node (ref "U1") (pin "9") (pinfunction "GPIO5/RTC_GPIO5/_TOUCH5/_ADC1_CH4_9") (pintype "passive"))
    )
    (net (code "36") (name "/GPIO6") (class "Default")
      (node (ref "J1") (pin "9") (pinfunction "9_9") (pintype "passive"))
      (node (ref "U1") (pin "10") (pinfunction "GPIO6/RTC_GPIO6/_TOUCH6/_ADC1_CH5_10") (pintype "passive"))
    )
    (net (code "37") (name "/GPIO7") (class "Default")
      (node (ref "J1") (pin "10") (pinfunction "10_10") (pintype "passive"))
      (node (ref "U1") (pin "11") (pinfunction "GPIO7/_RTC_GPIO7/TOUCH7/_ADC1_CH6_11") (pintype "passive"))
    )
    (net (code "38") (name "/GPIO8") (class "Default")
      (node (ref "J1") (pin "11") (pinfunction "11_11") (pintype "passive"))
      (node (ref "U1") (pin "12") (pinfunction "GPIO8/RTC_GPIO8/_TOUCH8/_ADC1_CH7/_SUBSPICS1_12") (pintype "passive"))
    )
    (net (code "39") (name "/GPIO9") (class "Default")
      (node (ref "J1") (pin "12") (pinfunction "12_12") (pintype "passive"))
      (node (ref "U1") (pin "13") (pinfunction "GPIO9/RTC_GPIO9/_TOUCH9/_ADC1_CH8/_FSPIHD/_SUBSPIHD_13") (pintype "passive"))
    )
    (net (code "40") (name "/GPIO10") (class "Default")
      (node (ref "J1") (pin "13") (pinfunction "13_13") (pintype "passive"))
      (node (ref "U1") (pin "14") (pinfunction "GPIO10/RTC_GPIO10/_TOUCH10/_ADC1_CH9/_FSPICS0/_FSPIIO4/_SUBSPICS0_14") (pintype "passive"))
    )
    (net (code "41") (name "/GPIO11") (class "Default")
      (node (ref "J1") (pin "14") (pinfunction "14_14") (pintype "passive"))
      (node (ref "U1") (pin "15") (pinfunction "GPIO11/RTC_GPIO11/_TOUCH11/_ADC2_CH0/_FSPID/_FSPIIO5/_SUBSPID_15") (pintype "passive"))
    )
    (net (code "42") (name "/GPIO12") (class "Default")
      (node (ref "J1") (pin "15") (pinfunction "15_15") (pintype "passive"))
      (node (ref "U1") (pin "16") (pinfunction "GPIO12/_RTC_GPIO12/TOUCH12/_ADC2_CH1/_FSPICLK/_FSPIIO6/_SUBSPICLK_16") (pintype "passive"))
    )
    (net (code "43") (name "/GPIO13") (class "Default")
      (node (ref "J1") (pin "16") (pinfunction "16_16") (pintype "passive"))
      (node (ref "U1") (pin "17") (pinfunction "GPIO13/RTC_GPIO13/_TOUCH13/_ADC2_CH2/_FSPIQ/_FSPIIO7/_SUBSPIQ_17") (pintype "passive"))
    )
    (net (code "44") (name "/GPIO14") (class "Default")
      (node (ref "J1") (pin "17") (pinfunction "17_17") (pintype "passive"))
      (node (ref "U1") (pin "18") (pinfunction "GPIO14/RTC_GPIO14/_TOUCH14/_ADC2_CH3/_FSPIWP/_FSPIDQS/_SUBSPIWP_18") (pintype "passive"))
    )
    (net (code "45") (name "/GPIO15") (class "Default")
      (node (ref "J1") (pin "18") (pinfunction "18_18") (pintype "passive"))
      (node (ref "U1") (pin "19") (pinfunction "GPIO15/RTC_GPIO15/_U0RTS/_ADC2_CH4/_XTAL_32K_P_19") (pintype "passive"))
    )
    (net (code "46") (name "/GPIO16") (class "Default")
      (node (ref "J1") (pin "19") (pinfunction "19_19") (pintype "passive"))
      (node (ref "U1") (pin "20") (pinfunction "GPIO16/URTC_GPIO16/0CTS/_ADC2_CH5/_XTAL_32K_N_20") (pintype "passive"))
    )
    (net (code "47") (name "/GPIO17") (class "Default")
      (node (ref "J1") (pin "20") (pinfunction "20_20") (pintype "passive"))
      (node (ref "U1") (pin "21") (pinfunction "GPIO17/RTC_GPIO17/_U1TXD/_ADC2_CH6_21") (pintype "passive"))
    )
    (net (code "48") (name "/GPIO18") (class "Default")
      (node (ref "J1") (pin "21") (pinfunction "21_21") (pintype "passive"))
      (node (ref "U1") (pin "22") (pinfunction "GPIO18/RTC_GPIO18/_U1RXD/_ADC2_CH7/_CLK_OUT3_22") (pintype "passive"))
    )
    (net (code "49") (name "/GPIO21") (class "Default")
      (node (ref "J2") (pin "19") (pinfunction "19_19") (pintype "passive"))
      (node (ref "U1") (pin "25") (pinfunction "GPIO21/RTC_GPIO21/_25") (pintype "passive"))
    )
    (net (code "50") (name "/GPIO26") (class "Default")
      (node (ref "J2") (pin "18") (pinfunction "18_18") (pintype "passive"))
      (node (ref "U1") (pin "26") (pinfunction "GPIO26/SPICS1/_26") (pintype "passive"))
    )
    (net (code "51") (name "/GPIO33") (class "Default")
      (node (ref "J2") (pin "17") (pinfunction "17_17") (pintype "passive"))
      (node (ref "U1") (pin "28") (pinfunction "GPIO33/SPIIO4/_FSPIHD/_SUBSPIHD_28") (pintype "passive"))
    )
    (net (code "52") (name "/GPIO34") (class "Default")
      (node (ref "J2") (pin "16") (pinfunction "16_16") (pintype "passive"))
      (node (ref "U1") (pin "29") (pinfunction "GPIO34/_SPIIO5/GPIO34/_FSPICS0/_SUBSPICS0_29") (pintype "passive"))
    )
    (net (code "53") (name "/GPIO35") (class "Default")
      (node (ref "J2") (pin "15") (pinfunction "15_15") (pintype "passive"))
      (node (ref "U1") (pin "31") (pinfunction "GPIO35/SPIIO6/_FSPID/_SUBSPID_31") (pintype "passive"))
    )
    (net (code "54") (name "/GPIO36") (class "Default")
      (node (ref "J2") (pin "14") (pinfunction "14_14") (pintype "passive"))
      (node (ref "U1") (pin "32") (pinfunction "GPIO36/SPIIO7/FSPICLK/_SUBSPICLK_32") (pintype "passive"))
    )
    (net (code "55") (name "/GPIO37") (class "Default")
      (node (ref "J2") (pin "13") (pinfunction "13_13") (pintype "passive"))
      (node (ref "U1") (pin "33") (pinfunction "GPIO37/SPIDQS/_FSPIQ/_SUBSPIQ_33") (pintype "passive"))
    )
    (net (code "56") (name "/GPIO38") (class "Default")
      (node (ref "J2") (pin "12") (pinfunction "12_12") (pintype "passive"))
      (node (ref "U1") (pin "34") (pinfunction "GPIO38/_FSPIWP/_SUBSPIWP_34") (pintype "passive"))
    )
    (net (code "57") (name "/GPIO39") (class "Default")
      (node (ref "J2") (pin "11") (pinfunction "11_11") (pintype "passive"))
      (node (ref "U1") (pin "35") (pinfunction "MTCK/_GPIO39/_CLK_OUT3/_SUBSPICS1_35") (pintype "passive"))
    )
    (net (code "58") (name "/GPIO40") (class "Default")
      (node (ref "J2") (pin "10") (pinfunction "10_10") (pintype "passive"))
      (node (ref "U1") (pin "36") (pinfunction "MTDO/_GPIO40/_CLK_OUT2_36") (pintype "passive"))
    )
    (net (code "59") (name "/GPIO41") (class "Default")
      (node (ref "J2") (pin "9") (pinfunction "9_9") (pintype "passive"))
      (node (ref "U1") (pin "37") (pinfunction "MTDI/_GPIO41/_CLK_OUT1_37") (pintype "passive"))
    )
    (net (code "60") (name "/GPIO42") (class "Default")
      (node (ref "J2") (pin "8") (pinfunction "8_8") (pintype "passive"))
      (node (ref "U1") (pin "38") (pinfunction "MTMS/_GPIO42_38") (pintype "passive"))
    )
    (net (code "61") (name "/GPIO45") (class "Default")
      (node (ref "J2") (pin "5") (pinfunction "5_5") (pintype "passive"))
      (node (ref "U1") (pin "41") (pinfunction "GPIO45_41") (pintype "passive"))
    )
    (net (code "62") (name "/GPIO46") (class "Default")
      (node (ref "J2") (pin "4") (pinfunction "4_4") (pintype "passive"))
      (node (ref "U1") (pin "44") (pinfunction "GPI046_44") (pintype "passive"))
    )
    (net (code "63") (name "/GPIO47") (class "Default")
      (node (ref "J2") (pin "23") (pinfunction "23_23") (pintype "passive"))
      (node (ref "U1") (pin "27") (pinfunction "GPIO47/SPICLK_P_DIFF/SUBSPICLK_P_DIFF_27") (pintype "passive"))
    )
    (net (code "64") (name "/GPIO48") (class "Default")
      (node (ref "J2") (pin "22") (pinfunction "22_22") (pintype "passive"))
      (node (ref "U1") (pin "30") (pinfunction "GPIO48/SPICLK_N_DIFF/_SUBSPICLK_N_DIFF_30") (pintype "passive"))
    )
    (net (code "65") (name "/RTS FTDI") (class "Default")
      (node (ref "Q1") (pin "2") (pinfunction "E_2") (pintype "passive"))
      (node (ref "R18") (pin "2") (pinfunction "2_2") (pintype "passive"))
      (node (ref "U2") (pin "19") (pinfunction "~{RTS}_19") (pintype "passive"))
    )
    (net (code "66") (name "/RXD  FTDI") (class "Default")
      (node (ref "U2") (pin "1") (pinfunction "RXD_1") (pintype "passive+no_connect"))
    )
    (net (code "67") (name "/RXD FTDI") (class "Default")
      (node (ref "R19") (pin "1") (pinfunction "1_1") (pintype "passive+no_connect"))
    )
    (net (code "68") (name "/TXD  FTDI") (class "Default")
      (node (ref "R20") (pin "1") (pinfunction "1_1") (pintype "passive"))
      (node (ref "U2") (pin "17") (pinfunction "TXD_17") (pintype "passive"))
    )
    (net (code "69") (name "/U0RXD") (class "Default")
      (node (ref "J2") (pin "6") (pinfunction "6_6") (pintype "passive"))
      (node (ref "R20") (pin "2") (pinfunction "2_2") (pintype "passive"))
      (node (ref "U1") (pin "40") (pinfunction "U0RXD/_GPIO44/_CLK_OUT2_40") (pintype "passive"))
    )
    (net (code "70") (name "/U0TXD") (class "Default")
      (node (ref "J2") (pin "7") (pinfunction "7_7") (pintype "passive"))
      (node (ref "R19") (pin "2") (pinfunction "2_2") (pintype "passive"))
      (node (ref "U1") (pin "39") (pinfunction "U0TXD/_GPIO43/_CLK_OUT1_39") (pintype "passive"))
    )
    (net (code "71") (name "/VBUS_SENSE") (class "Default")
      (node (ref "R13") (pin "2") (pinfunction "2_2") (pintype "passive"))
      (node (ref "R9") (pin "1") (pinfunction "1_1") (pintype "passive"))
      (node (ref "U2") (pin "16") (pinfunction "CBUS3_16") (pintype "passive"))
    )
    (net (code "72") (name "GND") (class "Default")
      (node (ref "4u7,16v") (pin "1") (pinfunction "1_1") (pintype "passive"))
      (node (ref "C1") (pin "1") (pinfunction "1_1") (pintype "passive"))
      (node (ref "C10") (pin "1") (pinfunction "1_1") (pintype "passive"))
      (node (ref "C11") (pin "1") (pinfunction "1_1") (pintype "passive"))
      (node (ref "C12") (pin "1") (pinfunction "1_1") (pintype "passive"))
      (node (ref "C13") (pin "1") (pinfunction "1_1") (pintype "passive"))
      (node (ref "C14") (pin "1") (pinfunction "1_1") (pintype "passive"))
      (node (ref "C15") (pin "1") (pinfunction "1_1") (pintype "passive"))
      (node (ref "C16") (pin "1") (pinfunction "1_1") (pintype "passive"))
      (node (ref "C2") (pin "1") (pinfunction "1_1") (pintype "passive"))
      (node (ref "C3") (pin "1") (pinfunction "1_1") (pintype "passive"))
      (node (ref "C4") (pin "1") (pinfunction "1_1") (pintype "passive"))
      (node (ref "C5") (pin "1") (pinfunction "1_1") (pintype "passive"))
      (node (ref "C6") (pin "1") (pinfunction "1_1") (pintype "passive"))
      (node (ref "C7") (pin "1") (pinfunction "1_1") (pintype "passive"))
      (node (ref "C8") (pin "1") (pinfunction "1_1") (pintype "passive"))
      (node (ref "C9") (pin "1") (pinfunction "1_1") (pintype "passive"))
      (node (ref "D1") (pin "1") (pinfunction "1_1") (pintype "passive"))
      (node (ref "D3") (pin "1") (pinfunction "1_1") (pintype "passive"))
      (node (ref "D4") (pin "1") (pinfunction "1_1") (pintype "passive"))
      (node (ref "D5") (pin "1") (pinfunction "1_1") (pintype "passive"))
      (node (ref "D6") (pin "1") (pinfunction "1_1") (pintype "passive"))
      (node (ref "D7") (pin "1") (pinfunction "1_1") (pintype "passive"))
      (node (ref "D8") (pin "1") (pinfunction "1_1") (pintype "passive"))
      (node (ref "J1") (pin "1") (pinfunction "1_1") (pintype "passive"))
      (node (ref "J1") (pin "23") (pinfunction "23_23") (pintype "passive"))
      (node (ref "J2") (pin "2") (pinfunction "2_2") (pintype "passive"))
      (node (ref "J2") (pin "24") (pinfunction "24_24") (pintype "passive"))
      (node (ref "J3") (pin "A1B12") (pinfunction "GND_A1B12_A1B12") (pintype "passive"))
      (node (ref "J3") (pin "B1A12") (pinfunction "GND_B1A12_B1A12") (pintype "passive"))
      (node (ref "J3") (pin "S1") (pinfunction "SHELD_1_S1") (pintype "passive"))
      (node (ref "J3") (pin "S2") (pinfunction "SHELD_2_S2") (pintype "passive"))
      (node (ref "J3") (pin "S3") (pinfunction "SHELD_3_S3") (pintype "passive"))
      (node (ref "J3") (pin "S4") (pinfunction "SHELD_4_S4") (pintype "passive"))
      (node (ref "J4") (pin "A1B12") (pinfunction "GND_A1B12_A1B12") (pintype "passive"))
      (node (ref "J4") (pin "A5") (pinfunction "_CC1_A5") (pintype "passive"))
      (node (ref "J4") (pin "B1A12") (pinfunction "GND_B1A12_B1A12") (pintype "passive"))
      (node (ref "J4") (pin "S1") (pinfunction "SHELD_1_S1") (pintype "passive"))
      (node (ref "J4") (pin "S2") (pinfunction "SHELD_2_S2") (pintype "passive"))
      (node (ref "J4") (pin "S3") (pinfunction "SHELD_3_S3") (pintype "passive"))
      (node (ref "J4") (pin "S4") (pinfunction "SHELD_4_S4") (pintype "passive"))
      (node (ref "R10") (pin "1") (pinfunction "1_1") (pintype "passive"))
      (node (ref "R11") (pin "1") (pinfunction "1_1") (pintype "passive"))
      (node (ref "R12") (pin "1") (pinfunction "1_1") (pintype "passive"))
      (node (ref "R13") (pin "1") (pinfunction "1_1") (pintype "passive"))
      (node (ref "R14") (pin "1") (pinfunction "1_1") (pintype "passive"))
      (node (ref "R14") (pin "2") (pinfunction "2_2") (pintype "passive"))
      (node (ref "R15") (pin "1") (pinfunction "1_1") (pintype "passive"))
      (node (ref "R15") (pin "2") (pinfunction "2_2") (pintype "passive"))
      (node (ref "SW1") (pin "3") (pinfunction "3_3") (pintype "passive"))
      (node (ref "SW1") (pin "4") (pinfunction "4_4") (pintype "passive"))
      (node (ref "SW2") (pin "3") (pinfunction "3_3") (pintype "passive"))
      (node (ref "SW2") (pin "4") (pinfunction "4_4") (pintype "passive"))
      (node (ref "U1") (pin "1") (pinfunction "GND_1_1") (pintype "passive"))
      (node (ref "U1") (pin "2") (pinfunction "GND_2_2") (pintype "passive"))
      (node (ref "U1") (pin "42") (pinfunction "GND_42") (pintype "passive"))
      (node (ref "U1") (pin "43") (pinfunction "GND_43") (pintype "passive"))
      (node (ref "U1") (pin "46") (pinfunction "GND_46_46") (pintype "passive"))
      (node (ref "U1") (pin "47") (pinfunction "GND_47_47") (pintype "passive"))
      (node (ref "U1") (pin "48") (pinfunction "GND_48_48") (pintype "passive"))
      (node (ref "U1") (pin "49") (pinfunction "GND_49_49") (pintype "passive"))
      (node (ref "U1") (pin "50") (pinfunction "GND_50_50") (pintype "passive"))
      (node (ref "U1") (pin "51") (pinfunction "GND_51_51") (pintype "passive"))
      (node (ref "U1") (pin "52") (pinfunction "GND_52_52") (pintype "passive"))
      (node (ref "U1") (pin "53") (pinfunction "GND_53_53") (pintype "passive"))
      (node (ref "U1") (pin "54") (pinfunction "GND_54_54") (pintype "passive"))
      (node (ref "U1") (pin "55") (pinfunction "GND_55_55") (pintype "passive"))
      (node (ref "U1") (pin "56") (pinfunction "GND_56_56") (pintype "passive"))
      (node (ref "U1") (pin "57") (pinfunction "GND_57_57") (pintype "passive"))
      (node (ref "U1") (pin "58") (pinfunction "GND_58_58") (pintype "passive"))
      (node (ref "U1") (pin "59") (pinfunction "GND_59_59") (pintype "passive"))
      (node (ref "U1") (pin "60") (pinfunction "GND_60_60") (pintype "passive"))
      (node (ref "U1") (pin "61") (pinfunction "GND_61_61") (pintype "passive"))
      (node (ref "U1") (pin "62") (pinfunction "GND_62_62") (pintype "passive"))
      (node (ref "U1") (pin "63") (pinfunction "GND_63_63") (pintype "passive"))
      (node (ref "U1") (pin "64") (pinfunction "GND_64_64") (pintype "passive"))
      (node (ref "U1") (pin "65") (pinfunction "GND_65_65") (pintype "passive"))
      (node (ref "U1") (pin "66") (pinfunction "GND_66_66") (pintype "passive"))
      (node (ref "U1") (pin "67") (pinfunction "GND_67_67") (pintype "passive"))
      (node (ref "U1") (pin "68") (pinfunction "GND_68_68") (pintype "passive"))
      (node (ref "U1") (pin "69") (pinfunction "GND_69_69") (pintype "passive"))
      (node (ref "U1") (pin "71") (pinfunction "GND_71_71") (pintype "passive"))
      (node (ref "U1") (pin "72") (pinfunction "GND_72_72") (pintype "passive"))
      (node (ref "U1") (pin "73") (pinfunction "GND_73_73") (pintype "passive"))
      (node (ref "U2") (pin "13") (pinfunction "GND_13") (pintype "passive"))
      (node (ref "U2") (pin "21") (pinfunction "GND_21") (pintype "passive"))
      (node (ref "U2") (pin "3") (pinfunction "GND_3") (pintype "passive"))
      (node (ref "U3") (pin "2") (pinfunction "GND_2") (pintype "power_in"))
      (node (ref "U3") (pin "4") (pinfunction "GND_4") (pintype "power_in"))
    )
    (net (code "73") (name "Net-(D1-Pad2)") (class "Default")
      (node (ref "D1") (pin "2") (pinfunction "2_2") (pintype "passive"))
      (node (ref "R4") (pin "1") (pinfunction "1_1") (pintype "passive"))
    )
    (net (code "74") (name "Net-(D2-Pad2)") (class "Default")
      (node (ref "D2") (pin "2") (pinfunction "2_2") (pintype "passive"))
      (node (ref "R3") (pin "1") (pinfunction "1_1") (pintype "passive"))
    )
    (net (code "75") (name "Net-(J3-CC2)") (class "Default")
      (node (ref "J3") (pin "B5") (pinfunction "CC2_B5") (pintype "passive"))
      (node (ref "R11") (pin "2") (pinfunction "2_2") (pintype "passive"))
    )
    (net (code "76") (name "Net-(J3-_CC1)") (class "Default")
      (node (ref "J3") (pin "A5") (pinfunction "_CC1_A5") (pintype "passive"))
      (node (ref "R12") (pin "2") (pinfunction "2_2") (pintype "passive"))
    )
    (net (code "77") (name "Net-(Q1-B)") (class "Default")
      (node (ref "Q1") (pin "1") (pinfunction "B_1") (pintype "passive"))
      (node (ref "R16") (pin "1") (pinfunction "1_1") (pintype "passive"))
    )
    (net (code "78") (name "Net-(Q2-B)") (class "Default")
      (node (ref "Q2") (pin "1") (pinfunction "B_1") (pintype "passive"))
      (node (ref "R18") (pin "1") (pinfunction "1_1") (pintype "passive"))
    )
    (net (code "79") (name "Net-(U2-CBUS0)") (class "Default")
      (node (ref "R10") (pin "2") (pinfunction "2_2") (pintype "passive"))
      (node (ref "U2") (pin "15") (pinfunction "CBUS0_15") (pintype "passive"))
    )
    (net (code "80") (name "Net-(U2-~{RESET})") (class "Default")
      (node (ref "C6") (pin "2") (pinfunction "2_2") (pintype "passive"))
      (node (ref "R8") (pin "1") (pinfunction "1_1") (pintype "passive"))
      (node (ref "U2") (pin "11") (pinfunction "~{RESET}_11") (pintype "passive"))
    )
    (net (code "81") (name "unconnected-(J1-Pad24)") (class "Default")
      (node (ref "J1") (pin "24") (pinfunction "24_24") (pintype "passive+no_connect"))
    )
    (net (code "82") (name "unconnected-(J3-SBU2-PadB8)") (class "Default")
      (node (ref "J3") (pin "B8") (pinfunction "SBU2_B8") (pintype "passive+no_connect"))
    )
    (net (code "83") (name "unconnected-(J3-_SBU2-PadA8)") (class "Default")
      (node (ref "J3") (pin "A8") (pinfunction "_SBU2_A8") (pintype "passive+no_connect"))
    )
    (net (code "84") (name "unconnected-(J4-CC2-PadB5)") (class "Default")
      (node (ref "J4") (pin "B5") (pinfunction "CC2_B5") (pintype "passive"))
    )
    (net (code "85") (name "unconnected-(J4-SBU2-PadB8)") (class "Default")
      (node (ref "J4") (pin "B8") (pinfunction "SBU2_B8") (pintype "passive+no_connect"))
    )
    (net (code "86") (name "unconnected-(J4-_SBU2-PadA8)") (class "Default")
      (node (ref "J4") (pin "A8") (pinfunction "_SBU2_A8") (pintype "passive"))
    )
    (net (code "87") (name "unconnected-(U1-GND_70-Pad70)") (class "Default")
      (node (ref "U1") (pin "70") (pinfunction "GND_70_70") (pintype "passive"))
    )
    (net (code "88") (name "unconnected-(U2-CBUS1-Pad14)") (class "Default")
      (node (ref "U2") (pin "14") (pinfunction "CBUS1_14") (pintype "passive+no_connect"))
    )
    (net (code "89") (name "unconnected-(U2-CBUS2-Pad7)") (class "Default")
      (node (ref "U2") (pin "7") (pinfunction "CBUS2_7") (pintype "passive+no_connect"))
    )
    (net (code "90") (name "unconnected-(U2-~{CTS}-Pad6)") (class "Default")
      (node (ref "U2") (pin "6") (pinfunction "~{CTS}_6") (pintype "passive+no_connect"))
    )
    (net (code "91") (name "unconnected-(U2-~{DCD}-Pad5)") (class "Default")
      (node (ref "U2") (pin "5") (pinfunction "~{DCD}_5") (pintype "passive+no_connect"))
    )
    (net (code "92") (name "unconnected-(U2-~{DSR}-Pad4)") (class "Default")
      (node (ref "U2") (pin "4") (pinfunction "~{DSR}_4") (pintype "passive+no_connect"))
    )
    (net (code "93") (name "unconnected-(U2-~{RI}-Pad2)") (class "Default")
      (node (ref "U2") (pin "2") (pinfunction "~{RI}_2") (pintype "passive+no_connect"))
    )
  )
)
